# SoM_Breakout.net
KiCad netlist of a schematic drawn in EAGLE
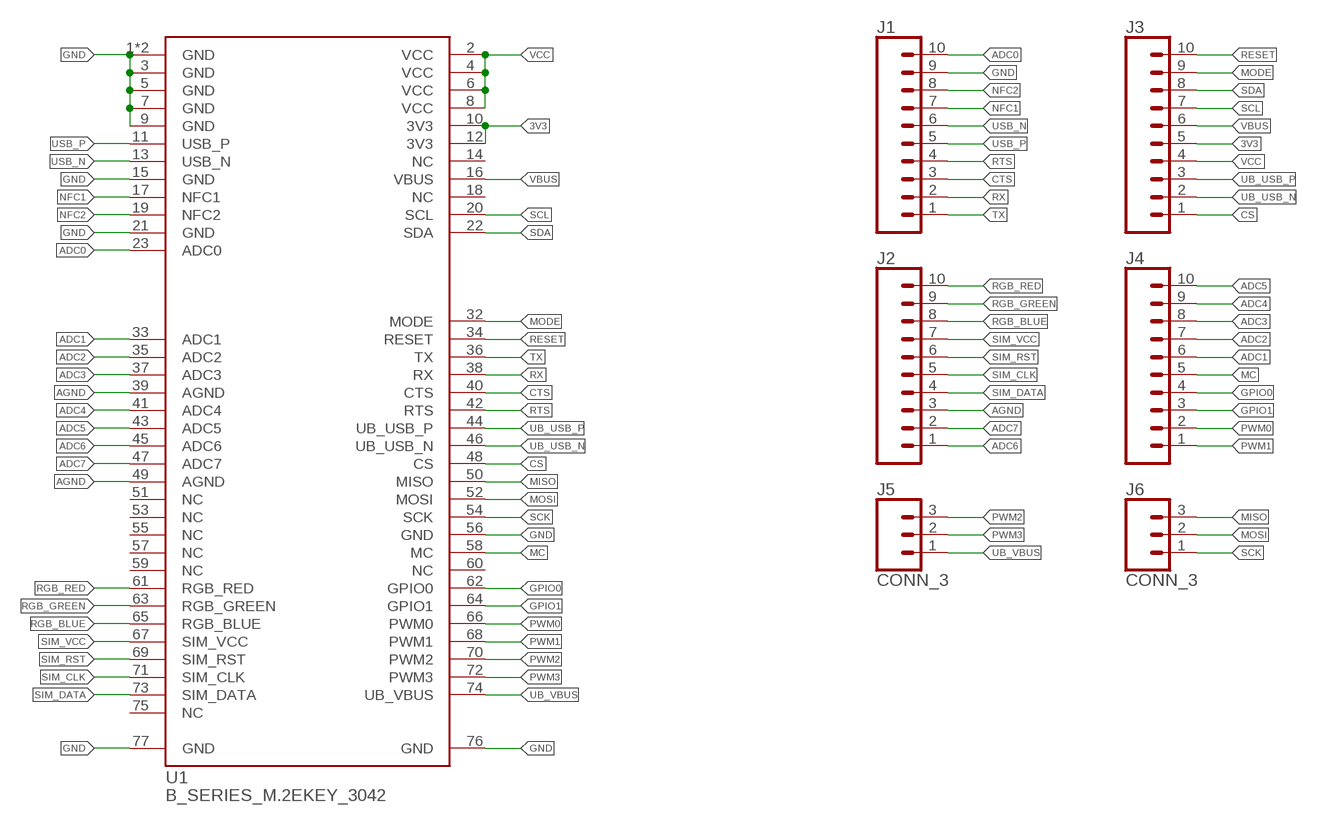
[diagram p0: schematic, sheet 1]

(export (version "E")
  (design (tool "Eeschema 10.0.6"))
  (components
    (comp (ref "J1")
      (value "CONN_10\"")
      (footprint "eagle-import:1X10")
      (libsource (lib "eagle-import") (part "CONN_10{dblquote}"))
    )
    (comp (ref "J2")
      (value "CONN_10\"")
      (footprint "eagle-import:1X10")
      (libsource (lib "eagle-import") (part "CONN_10{dblquote}"))
    )
    (comp (ref "J3")
      (value "CONN_10\"")
      (footprint "eagle-import:1X10")
      (libsource (lib "eagle-import") (part "CONN_10{dblquote}"))
    )
    (comp (ref "J4")
      (value "CONN_10\"")
      (footprint "eagle-import:1X10")
      (libsource (lib "eagle-import") (part "CONN_10{dblquote}"))
    )
    (comp (ref "J5")
      (value "CONN_3")
      (footprint "eagle-import:1X03")
      (libsource (lib "eagle-import") (part "CONN_3"))
    )
    (comp (ref "J6")
      (value "CONN_3")
      (footprint "eagle-import:1X03")
      (libsource (lib "eagle-import") (part "CONN_3"))
    )
    (comp (ref "U1")
      (value "B_SERIES_M.2EKEY_3042")
      (footprint "eagle-import:PARTICLE_M.2EKEY")
      (libsource (lib "eagle-import") (part "B_SERIES_M.2EKEY_3042"))
    )
  )
  (nets
    (net (code "1") (name "3V3") (class "Default")
      (node (ref "J3") (pin "5") (pinfunction "5_5") (pintype "passive"))
      (node (ref "U1") (pin "10") (pinfunction "3V3_10") (pintype "power_in"))
      (node (ref "U1") (pin "12") (pinfunction "3V3_12") (pintype "power_in"))
    )
    (net (code "2") (name "ADC0") (class "Default")
      (node (ref "J1") (pin "10") (pinfunction "10_10") (pintype "passive"))
      (node (ref "U1") (pin "23") (pinfunction "ADC0_23") (pintype "bidirectional"))
    )
    (net (code "3") (name "ADC1") (class "Default")
      (node (ref "J4") (pin "6") (pinfunction "6_6") (pintype "passive"))
      (node (ref "U1") (pin "33") (pinfunction "ADC1_33") (pintype "bidirectional"))
    )
    (net (code "4") (name "ADC2") (class "Default")
      (node (ref "J4") (pin "7") (pinfunction "7_7") (pintype "passive"))
      (node (ref "U1") (pin "35") (pinfunction "ADC2_35") (pintype "bidirectional"))
    )
    (net (code "5") (name "ADC3") (class "Default")
      (node (ref "J4") (pin "8") (pinfunction "8_8") (pintype "passive"))
      (node (ref "U1") (pin "37") (pinfunction "ADC3_37") (pintype "bidirectional"))
    )
    (net (code "6") (name "ADC4") (class "Default")
      (node (ref "J4") (pin "9") (pinfunction "9_9") (pintype "passive"))
      (node (ref "U1") (pin "41") (pinfunction "ADC4_41") (pintype "bidirectional"))
    )
    (net (code "7") (name "ADC5") (class "Default")
      (node (ref "J4") (pin "10") (pinfunction "10_10") (pintype "passive"))
      (node (ref "U1") (pin "43") (pinfunction "ADC5_43") (pintype "bidirectional"))
    )
    (net (code "8") (name "ADC6") (class "Default")
      (node (ref "J2") (pin "1") (pinfunction "1_1") (pintype "passive"))
      (node (ref "U1") (pin "45") (pinfunction "ADC6_45") (pintype "bidirectional"))
    )
    (net (code "9") (name "ADC7") (class "Default")
      (node (ref "J2") (pin "2") (pinfunction "2_2") (pintype "passive"))
      (node (ref "U1") (pin "47") (pinfunction "ADC7_47") (pintype "bidirectional"))
    )
    (net (code "10") (name "AGND") (class "Default")
      (node (ref "J2") (pin "3") (pinfunction "3_3") (pintype "passive"))
      (node (ref "U1") (pin "39") (pinfunction "AGND_39") (pintype "power_in"))
      (node (ref "U1") (pin "49") (pinfunction "AGND_49") (pintype "power_in"))
    )
    (net (code "11") (name "CS") (class "Default")
      (node (ref "J3") (pin "1") (pinfunction "1_1") (pintype "passive"))
      (node (ref "U1") (pin "48") (pinfunction "CS_48") (pintype "bidirectional"))
    )
    (net (code "12") (name "CTS") (class "Default")
      (node (ref "J1") (pin "3") (pinfunction "3_3") (pintype "passive"))
      (node (ref "U1") (pin "40") (pinfunction "CTS_40") (pintype "bidirectional"))
    )
    (net (code "13") (name "GND") (class "Default")
      (node (ref "J1") (pin "9") (pinfunction "9_9") (pintype "passive"))
      (node (ref "U1") (pin "1") (pinfunction "GND_1") (pintype "power_in"))
      (node (ref "U1") (pin "15") (pinfunction "GND_15") (pintype "power_in"))
      (node (ref "U1") (pin "21") (pinfunction "GND_21") (pintype "power_in"))
      (node (ref "U1") (pin "3") (pinfunction "GND_3") (pintype "power_in"))
      (node (ref "U1") (pin "5") (pinfunction "GND_5") (pintype "power_in"))
      (node (ref "U1") (pin "56") (pinfunction "GND_56") (pintype "power_in"))
      (node (ref "U1") (pin "7") (pinfunction "GND_7") (pintype "power_in"))
      (node (ref "U1") (pin "76") (pinfunction "GND_76") (pintype "power_in"))
      (node (ref "U1") (pin "77") (pinfunction "GND_77") (pintype "power_in"))
      (node (ref "U1") (pin "9") (pinfunction "GND_9") (pintype "power_in"))
      (node (ref "U1") (pin "GND") (pinfunction "GND_GND") (pintype "power_in"))
    )
    (net (code "14") (name "GPIO0") (class "Default")
      (node (ref "J4") (pin "4") (pinfunction "4_4") (pintype "passive"))
      (node (ref "U1") (pin "62") (pinfunction "GPIO0_62") (pintype "bidirectional"))
    )
    (net (code "15") (name "GPIO1") (class "Default")
      (node (ref "J4") (pin "3") (pinfunction "3_3") (pintype "passive"))
      (node (ref "U1") (pin "64") (pinfunction "GPIO1_64") (pintype "bidirectional"))
    )
    (net (code "16") (name "MC") (class "Default")
      (node (ref "J4") (pin "5") (pinfunction "5_5") (pintype "passive"))
      (node (ref "U1") (pin "58") (pinfunction "MC_58") (pintype "bidirectional"))
    )
    (net (code "17") (name "MISO") (class "Default")
      (node (ref "J6") (pin "3") (pinfunction "3_3") (pintype "passive"))
      (node (ref "U1") (pin "50") (pinfunction "MISO_50") (pintype "bidirectional"))
    )
    (net (code "18") (name "MODE") (class "Default")
      (node (ref "J3") (pin "9") (pinfunction "9_9") (pintype "passive"))
      (node (ref "U1") (pin "32") (pinfunction "MODE_32") (pintype "bidirectional"))
    )
    (net (code "19") (name "MOSI") (class "Default")
      (node (ref "J6") (pin "2") (pinfunction "2_2") (pintype "passive"))
      (node (ref "U1") (pin "52") (pinfunction "MOSI_52") (pintype "bidirectional"))
    )
    (net (code "20") (name "NFC1") (class "Default")
      (node (ref "J1") (pin "7") (pinfunction "7_7") (pintype "passive"))
      (node (ref "U1") (pin "17") (pinfunction "NFC1_17") (pintype "bidirectional"))
    )
    (net (code "21") (name "NFC2") (class "Default")
      (node (ref "J1") (pin "8") (pinfunction "8_8") (pintype "passive"))
      (node (ref "U1") (pin "19") (pinfunction "NFC2_19") (pintype "bidirectional"))
    )
    (net (code "22") (name "PWM0") (class "Default")
      (node (ref "J4") (pin "2") (pinfunction "2_2") (pintype "passive"))
      (node (ref "U1") (pin "66") (pinfunction "PWM0_66") (pintype "bidirectional"))
    )
    (net (code "23") (name "PWM1") (class "Default")
      (node (ref "J4") (pin "1") (pinfunction "1_1") (pintype "passive"))
      (node (ref "U1") (pin "68") (pinfunction "PWM1_68") (pintype "bidirectional"))
    )
    (net (code "24") (name "PWM2") (class "Default")
      (node (ref "J5") (pin "3") (pinfunction "3_3") (pintype "passive"))
      (node (ref "U1") (pin "70") (pinfunction "PWM2_70") (pintype "bidirectional"))
    )
    (net (code "25") (name "PWM3") (class "Default")
      (node (ref "J5") (pin "2") (pinfunction "2_2") (pintype "passive"))
      (node (ref "U1") (pin "72") (pinfunction "PWM3_72") (pintype "bidirectional"))
    )
    (net (code "26") (name "RESET") (class "Default")
      (node (ref "J3") (pin "10") (pinfunction "10_10") (pintype "passive"))
      (node (ref "U1") (pin "34") (pinfunction "RESET_34") (pintype "bidirectional"))
    )
    (net (code "27") (name "RGB_BLUE") (class "Default")
      (node (ref "J2") (pin "8") (pinfunction "8_8") (pintype "passive"))
      (node (ref "U1") (pin "65") (pinfunction "RGB_BLUE_65") (pintype "bidirectional"))
    )
    (net (code "28") (name "RGB_GREEN") (class "Default")
      (node (ref "J2") (pin "9") (pinfunction "9_9") (pintype "passive"))
      (node (ref "U1") (pin "63") (pinfunction "RGB_GREEN_63") (pintype "bidirectional"))
    )
    (net (code "29") (name "RGB_RED") (class "Default")
      (node (ref "J2") (pin "10") (pinfunction "10_10") (pintype "passive"))
      (node (ref "U1") (pin "61") (pinfunction "RGB_RED_61") (pintype "bidirectional"))
    )
    (net (code "30") (name "RTS") (class "Default")
      (node (ref "J1") (pin "4") (pinfunction "4_4") (pintype "passive"))
      (node (ref "U1") (pin "42") (pinfunction "RTS_42") (pintype "bidirectional"))
    )
    (net (code "31") (name "RX") (class "Default")
      (node (ref "J1") (pin "2") (pinfunction "2_2") (pintype "passive"))
      (node (ref "U1") (pin "38") (pinfunction "RX_38") (pintype "bidirectional"))
    )
    (net (code "32") (name "SCK") (class "Default")
      (node (ref "J6") (pin "1") (pinfunction "1_1") (pintype "passive"))
      (node (ref "U1") (pin "54") (pinfunction "SCK_54") (pintype "bidirectional"))
    )
    (net (code "33") (name "SCL") (class "Default")
      (node (ref "J3") (pin "7") (pinfunction "7_7") (pintype "passive"))
      (node (ref "U1") (pin "20") (pinfunction "SCL_20") (pintype "bidirectional"))
    )
    (net (code "34") (name "SDA") (class "Default")
      (node (ref "J3") (pin "8") (pinfunction "8_8") (pintype "passive"))
      (node (ref "U1") (pin "22") (pinfunction "SDA_22") (pintype "bidirectional"))
    )
    (net (code "35") (name "SIM_CLK") (class "Default")
      (node (ref "J2") (pin "5") (pinfunction "5_5") (pintype "passive"))
      (node (ref "U1") (pin "71") (pinfunction "SIM_CLK_71") (pintype "bidirectional"))
    )
    (net (code "36") (name "SIM_DATA") (class "Default")
      (node (ref "J2") (pin "4") (pinfunction "4_4") (pintype "passive"))
      (node (ref "U1") (pin "73") (pinfunction "SIM_DATA_73") (pintype "bidirectional"))
    )
    (net (code "37") (name "SIM_RST") (class "Default")
      (node (ref "J2") (pin "6") (pinfunction "6_6") (pintype "passive"))
      (node (ref "U1") (pin "69") (pinfunction "SIM_RST_69") (pintype "bidirectional"))
    )
    (net (code "38") (name "SIM_VCC") (class "Default")
      (node (ref "J2") (pin "7") (pinfunction "7_7") (pintype "passive"))
      (node (ref "U1") (pin "67") (pinfunction "SIM_VCC_67") (pintype "power_in"))
    )
    (net (code "39") (name "TX") (class "Default")
      (node (ref "J1") (pin "1") (pinfunction "1_1") (pintype "passive"))
      (node (ref "U1") (pin "36") (pinfunction "TX_36") (pintype "bidirectional"))
    )
    (net (code "40") (name "UB_USB_N") (class "Default")
      (node (ref "J3") (pin "2") (pinfunction "2_2") (pintype "passive"))
      (node (ref "U1") (pin "46") (pinfunction "UB_USB_N_46") (pintype "bidirectional"))
    )
    (net (code "41") (name "UB_USB_P") (class "Default")
      (node (ref "J3") (pin "3") (pinfunction "3_3") (pintype "passive"))
      (node (ref "U1") (pin "44") (pinfunction "UB_USB_P_44") (pintype "bidirectional"))
    )
    (net (code "42") (name "UB_VBUS") (class "Default")
      (node (ref "J5") (pin "1") (pinfunction "1_1") (pintype "passive"))
      (node (ref "U1") (pin "74") (pinfunction "UB_VBUS_74") (pintype "power_in"))
    )
    (net (code "43") (name "USB_N") (class "Default")
      (node (ref "J1") (pin "6") (pinfunction "6_6") (pintype "passive"))
      (node (ref "U1") (pin "13") (pinfunction "USB_N_13") (pintype "bidirectional"))
    )
    (net (code "44") (name "USB_P") (class "Default")
      (node (ref "J1") (pin "5") (pinfunction "5_5") (pintype "passive"))
      (node (ref "U1") (pin "11") (pinfunction "USB_P_11") (pintype "bidirectional"))
    )
    (net (code "45") (name "VBUS") (class "Default")
      (node (ref "J3") (pin "6") (pinfunction "6_6") (pintype "passive"))
      (node (ref "U1") (pin "16") (pinfunction "VBUS_16") (pintype "power_in"))
    )
    (net (code "46") (name "VCC") (class "Default")
      (node (ref "J3") (pin "4") (pinfunction "4_4") (pintype "passive"))
      (node (ref "U1") (pin "2") (pinfunction "VCC_2") (pintype "power_in"))
      (node (ref "U1") (pin "4") (pinfunction "VCC_4") (pintype "power_in"))
      (node (ref "U1") (pin "6") (pinfunction "VCC_6") (pintype "power_in"))
      (node (ref "U1") (pin "8") (pinfunction "VCC_8") (pintype "power_in"))
    )
    (net (code "47") (name "unconnected-(U1B-NC-Pad14)") (class "Default")
      (node (ref "U1") (pin "14") (pinfunction "NC_14") (pintype "bidirectional"))
    )
    (net (code "48") (name "unconnected-(U1B-NC-Pad18)") (class "Default")
      (node (ref "U1") (pin "18") (pinfunction "NC_18") (pintype "bidirectional"))
    )
    (net (code "49") (name "unconnected-(U1B-NC-Pad51)") (class "Default")
      (node (ref "U1") (pin "51") (pinfunction "NC_51") (pintype "bidirectional"))
    )
    (net (code "50") (name "unconnected-(U1B-NC-Pad53)") (class "Default")
      (node (ref "U1") (pin "53") (pinfunction "NC_53") (pintype "bidirectional"))
    )
    (net (code "51") (name "unconnected-(U1B-NC-Pad55)") (class "Default")
      (node (ref "U1") (pin "55") (pinfunction "NC_55") (pintype "bidirectional"))
    )
    (net (code "52") (name "unconnected-(U1B-NC-Pad57)") (class "Default")
      (node (ref "U1") (pin "57") (pinfunction "NC_57") (pintype "bidirectional"))
    )
    (net (code "53") (name "unconnected-(U1B-NC-Pad59)") (class "Default")
      (node (ref "U1") (pin "59") (pinfunction "NC_59") (pintype "bidirectional"))
    )
    (net (code "54") (name "unconnected-(U1B-NC-Pad60)") (class "Default")
      (node (ref "U1") (pin "60") (pinfunction "NC_60") (pintype "bidirectional"))
    )
    (net (code "55") (name "unconnected-(U1B-NC-Pad75)") (class "Default")
      (node (ref "U1") (pin "75") (pinfunction "NC_75") (pintype "bidirectional"))
    )
  )
)
